# Active_Probe_Proto1.net
KiCad netlist of a schematic drawn in EAGLE
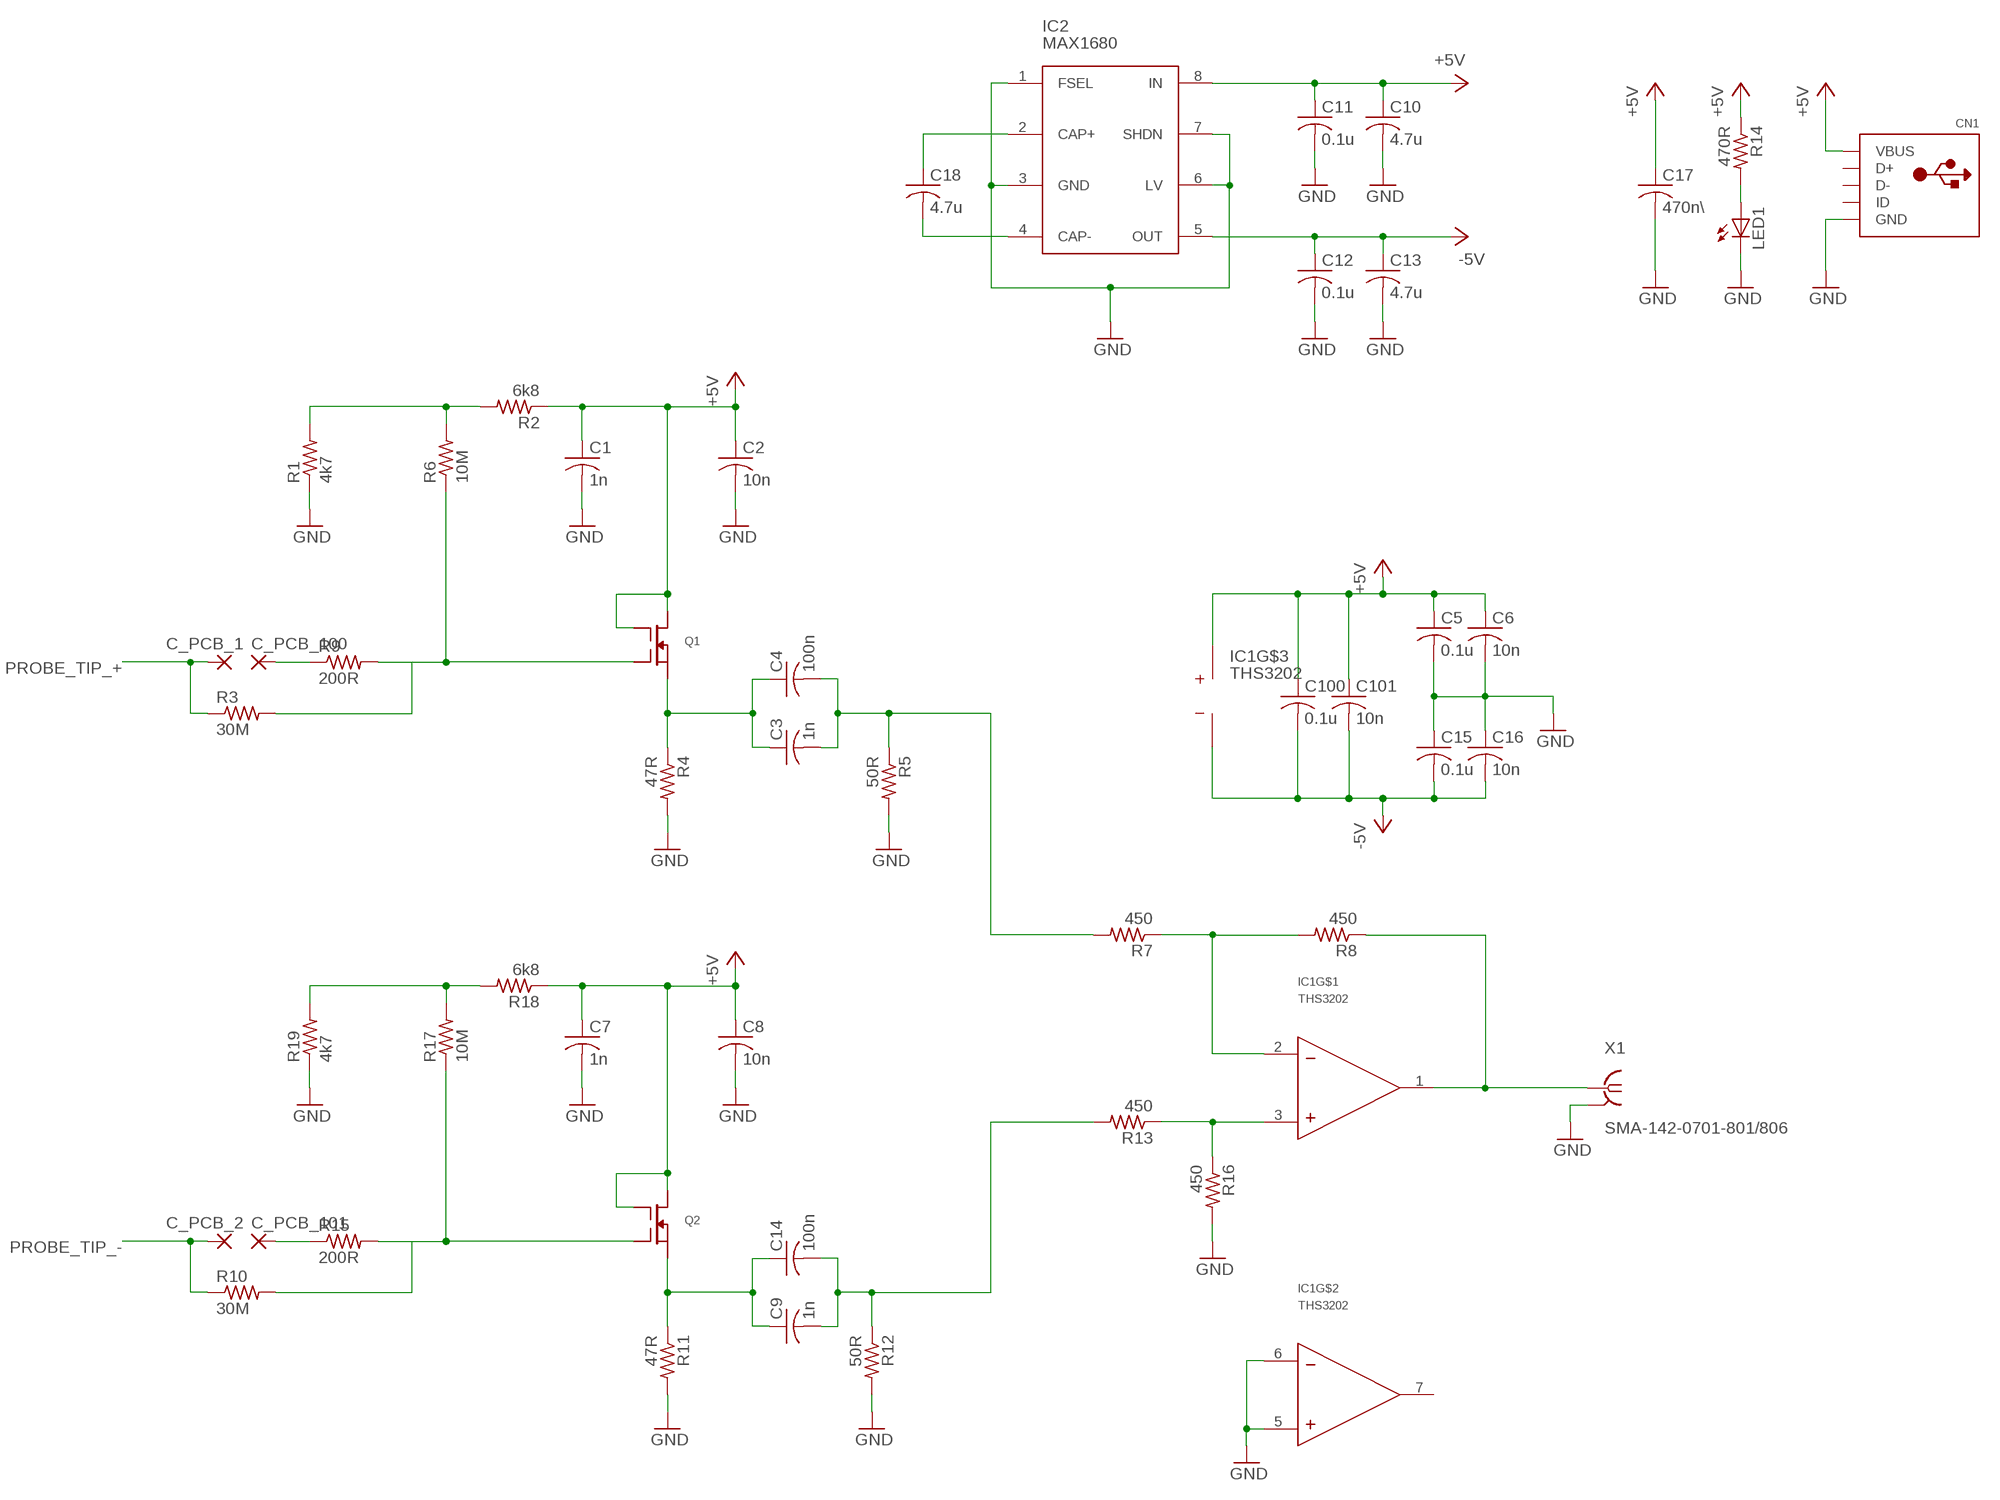
[diagram p0: schematic, sheet 1]

(export (version "E")
  (design (tool "Eeschema 10.0.6"))
  (components
    (comp (ref "C1")
      (value "1n")
      (footprint "eagle-import:C0805")
      (libsource (lib "eagle-import") (part "C-USC0805"))
    )
    (comp (ref "C2")
      (value "10n")
      (footprint "eagle-import:C0805")
      (libsource (lib "eagle-import") (part "C-USC0805"))
    )
    (comp (ref "C3")
      (value "1n")
      (footprint "eagle-import:C0805")
      (libsource (lib "eagle-import") (part "C-USC0805"))
    )
    (comp (ref "C4")
      (value "100n")
      (footprint "eagle-import:C0805")
      (libsource (lib "eagle-import") (part "C-USC0805"))
    )
    (comp (ref "C5")
      (value "0.1u")
      (footprint "eagle-import:C0805")
      (libsource (lib "eagle-import") (part "C-USC0805"))
    )
    (comp (ref "C6")
      (value "10n")
      (footprint "eagle-import:C0805")
      (libsource (lib "eagle-import") (part "C-USC0805"))
    )
    (comp (ref "C7")
      (value "1n")
      (footprint "eagle-import:C0805")
      (libsource (lib "eagle-import") (part "C-USC0805"))
    )
    (comp (ref "C8")
      (value "10n")
      (footprint "eagle-import:C0805")
      (libsource (lib "eagle-import") (part "C-USC0805"))
    )
    (comp (ref "C9")
      (value "1n")
      (footprint "eagle-import:C0805")
      (libsource (lib "eagle-import") (part "C-USC0805"))
    )
    (comp (ref "C10")
      (value "4.7u")
      (footprint "eagle-import:C0805")
      (libsource (lib "eagle-import") (part "C-USC0805"))
    )
    (comp (ref "C11")
      (value "0.1u")
      (footprint "eagle-import:C0805")
      (libsource (lib "eagle-import") (part "C-USC0805"))
    )
    (comp (ref "C12")
      (value "0.1u")
      (footprint "eagle-import:C0805")
      (libsource (lib "eagle-import") (part "C-USC0805"))
    )
    (comp (ref "C13")
      (value "4.7u")
      (footprint "eagle-import:C0805")
      (libsource (lib "eagle-import") (part "C-USC0805"))
    )
    (comp (ref "C14")
      (value "100n")
      (footprint "eagle-import:C0805")
      (libsource (lib "eagle-import") (part "C-USC0805"))
    )
    (comp (ref "C15")
      (value "0.1u")
      (footprint "eagle-import:C0805")
      (libsource (lib "eagle-import") (part "C-USC0805"))
    )
    (comp (ref "C16")
      (value "10n")
      (footprint "eagle-import:C0805")
      (libsource (lib "eagle-import") (part "C-USC0805"))
    )
    (comp (ref "C17")
      (value "470n\\")
      (footprint "eagle-import:C0805")
      (libsource (lib "eagle-import") (part "C-USC0805"))
    )
    (comp (ref "C18")
      (value "4.7u")
      (footprint "eagle-import:C0805")
      (libsource (lib "eagle-import") (part "C-USC0805"))
    )
    (comp (ref "C100")
      (value "0.1u")
      (footprint "eagle-import:C0805")
      (libsource (lib "eagle-import") (part "C-USC0805"))
    )
    (comp (ref "C101")
      (value "10n")
      (footprint "eagle-import:C0805")
      (libsource (lib "eagle-import") (part "C-USC0805"))
    )
    (comp (ref "CN1")
      (value "USBMINIB")
      (footprint "eagle-import:USB-MINIB")
      (libsource (lib "eagle-import") (part "USBMINIB"))
    )
    (comp (ref "C_PCB_1")
      (value "SMD5")
      (footprint "eagle-import:SMD2,54-5,08")
      (libsource (lib "eagle-import") (part "SMD5"))
    )
    (comp (ref "C_PCB_2")
      (value "SMD5")
      (footprint "eagle-import:SMD2,54-5,08")
      (libsource (lib "eagle-import") (part "SMD5"))
    )
    (comp (ref "C_PCB_100")
      (value "SMD5")
      (footprint "eagle-import:SMD2,54-5,08")
      (libsource (lib "eagle-import") (part "SMD5"))
    )
    (comp (ref "C_PCB_101")
      (value "SMD5")
      (footprint "eagle-import:SMD2,54-5,08")
      (libsource (lib "eagle-import") (part "SMD5"))
    )
    (comp (ref "IC1")
      (value "THS3202")
      (footprint "eagle-import:SOIC8")
      (libsource (lib "eagle-import") (part "THS3202"))
    )
    (comp (ref "IC2")
      (value "MAX1680")
      (footprint "eagle-import:SO8")
      (libsource (lib "eagle-import") (part "MAX1680/1"))
    )
    (comp (ref "LED1")
      (value "LED3MM")
      (footprint "eagle-import:LED3MM")
      (libsource (lib "eagle-import") (part "LED3MM"))
    )
    (comp (ref "Q1")
      (value "BF998")
      (footprint "eagle-import:SOT143B")
      (libsource (lib "eagle-import") (part "BF998"))
    )
    (comp (ref "Q2")
      (value "BF998")
      (footprint "eagle-import:SOT143B")
      (libsource (lib "eagle-import") (part "BF998"))
    )
    (comp (ref "R1")
      (value "4k7")
      (footprint "eagle-import:R0805")
      (libsource (lib "eagle-import") (part "R-US_R0805"))
    )
    (comp (ref "R2")
      (value "6k8")
      (footprint "eagle-import:R0805")
      (libsource (lib "eagle-import") (part "R-US_R0805"))
    )
    (comp (ref "R3")
      (value "30M")
      (footprint "eagle-import:R0805")
      (libsource (lib "eagle-import") (part "R-US_R0805"))
    )
    (comp (ref "R4")
      (value "47R")
      (footprint "eagle-import:R0805")
      (libsource (lib "eagle-import") (part "R-US_R0805"))
    )
    (comp (ref "R5")
      (value "50R")
      (footprint "eagle-import:R0805")
      (libsource (lib "eagle-import") (part "R-US_R0805"))
    )
    (comp (ref "R6")
      (value "10M")
      (footprint "eagle-import:R0805")
      (libsource (lib "eagle-import") (part "R-US_R0805"))
    )
    (comp (ref "R7")
      (value "450")
      (footprint "eagle-import:R0805")
      (libsource (lib "eagle-import") (part "R-US_R0805"))
    )
    (comp (ref "R8")
      (value "450")
      (footprint "eagle-import:R0805")
      (libsource (lib "eagle-import") (part "R-US_R0805"))
    )
    (comp (ref "R9")
      (value "200R")
      (footprint "eagle-import:R0805")
      (libsource (lib "eagle-import") (part "R-US_R0805"))
    )
    (comp (ref "R10")
      (value "30M")
      (footprint "eagle-import:R0805")
      (libsource (lib "eagle-import") (part "R-US_R0805"))
    )
    (comp (ref "R11")
      (value "47R")
      (footprint "eagle-import:R0805")
      (libsource (lib "eagle-import") (part "R-US_R0805"))
    )
    (comp (ref "R12")
      (value "50R")
      (footprint "eagle-import:R0805")
      (libsource (lib "eagle-import") (part "R-US_R0805"))
    )
    (comp (ref "R13")
      (value "450")
      (footprint "eagle-import:R0805")
      (libsource (lib "eagle-import") (part "R-US_R0805"))
    )
    (comp (ref "R14")
      (value "470R")
      (footprint "eagle-import:R0805")
      (libsource (lib "eagle-import") (part "R-US_R0805"))
    )
    (comp (ref "R15")
      (value "200R")
      (footprint "eagle-import:R0805")
      (libsource (lib "eagle-import") (part "R-US_R0805"))
    )
    (comp (ref "R16")
      (value "450")
      (footprint "eagle-import:R0805")
      (libsource (lib "eagle-import") (part "R-US_R0805"))
    )
    (comp (ref "R17")
      (value "10M")
      (footprint "eagle-import:R0805")
      (libsource (lib "eagle-import") (part "R-US_R0805"))
    )
    (comp (ref "R18")
      (value "6k8")
      (footprint "eagle-import:R0805")
      (libsource (lib "eagle-import") (part "R-US_R0805"))
    )
    (comp (ref "R19")
      (value "4k7")
      (footprint "eagle-import:R0805")
      (libsource (lib "eagle-import") (part "R-US_R0805"))
    )
    (comp (ref "X1")
      (value "SMA-142-0701-801/806")
      (footprint "eagle-import:J502-ND-142-0701-801_806")
      (fields (field (name "MF") "JOHNSON COMPONENTS") (field (name "MPN") "142-0701-801"))
      (libsource (lib "eagle-import") (part "SMA-142-0701-801/806"))
    )
  )
  (nets
    (net (code "1") (name "+5V") (class "Default")
      (node (ref "C1") (pin "1") (pinfunction "1_1") (pintype "passive"))
      (node (ref "C10") (pin "1") (pinfunction "1_1") (pintype "passive"))
      (node (ref "C100") (pin "1") (pinfunction "1_1") (pintype "passive"))
      (node (ref "C101") (pin "1") (pinfunction "1_1") (pintype "passive"))
      (node (ref "C11") (pin "1") (pinfunction "1_1") (pintype "passive"))
      (node (ref "C17") (pin "1") (pinfunction "1_1") (pintype "passive"))
      (node (ref "C2") (pin "1") (pinfunction "1_1") (pintype "passive"))
      (node (ref "C5") (pin "1") (pinfunction "1_1") (pintype "passive"))
      (node (ref "C6") (pin "1") (pinfunction "1_1") (pintype "passive"))
      (node (ref "C7") (pin "1") (pinfunction "1_1") (pintype "passive"))
      (node (ref "C8") (pin "1") (pinfunction "1_1") (pintype "passive"))
      (node (ref "CN1") (pin "VBUS") (pinfunction "VBUS_VBUS") (pintype "power_in"))
      (node (ref "IC1") (pin "8") (pinfunction "VCC_8") (pintype "power_in"))
      (node (ref "IC2") (pin "8") (pinfunction "IN_8") (pintype "bidirectional"))
      (node (ref "Q1") (pin "2") (pinfunction "D_2") (pintype "bidirectional"))
      (node (ref "Q1") (pin "3") (pinfunction "G2_3") (pintype "bidirectional"))
      (node (ref "Q2") (pin "2") (pinfunction "D_2") (pintype "bidirectional"))
      (node (ref "Q2") (pin "3") (pinfunction "G2_3") (pintype "bidirectional"))
      (node (ref "R14") (pin "1") (pinfunction "1_1") (pintype "passive"))
      (node (ref "R18") (pin "1") (pinfunction "1_1") (pintype "passive"))
      (node (ref "R2") (pin "1") (pinfunction "1_1") (pintype "passive"))
    )
    (net (code "2") (name "-5V") (class "Default")
      (node (ref "C100") (pin "2") (pinfunction "2_2") (pintype "passive"))
      (node (ref "C101") (pin "2") (pinfunction "2_2") (pintype "passive"))
      (node (ref "C12") (pin "1") (pinfunction "1_1") (pintype "passive"))
      (node (ref "C13") (pin "1") (pinfunction "1_1") (pintype "passive"))
      (node (ref "C15") (pin "2") (pinfunction "2_2") (pintype "passive"))
      (node (ref "C16") (pin "2") (pinfunction "2_2") (pintype "passive"))
      (node (ref "IC1") (pin "4") (pinfunction "GND_4") (pintype "power_in"))
      (node (ref "IC2") (pin "5") (pinfunction "OUT_5") (pintype "bidirectional"))
    )
    (net (code "3") (name "/PROBE_TIP_+") (class "Default")
      (node (ref "C_PCB_1") (pin "1") (pinfunction "P_1") (pintype "passive"))
      (node (ref "R3") (pin "1") (pinfunction "1_1") (pintype "passive"))
    )
    (net (code "4") (name "/PROBE_TIP_-") (class "Default")
      (node (ref "C_PCB_2") (pin "1") (pinfunction "P_1") (pintype "passive"))
      (node (ref "R10") (pin "1") (pinfunction "1_1") (pintype "passive"))
    )
    (net (code "5") (name "GND") (class "Default")
      (node (ref "C1") (pin "2") (pinfunction "2_2") (pintype "passive"))
      (node (ref "C10") (pin "2") (pinfunction "2_2") (pintype "passive"))
      (node (ref "C11") (pin "2") (pinfunction "2_2") (pintype "passive"))
      (node (ref "C12") (pin "2") (pinfunction "2_2") (pintype "passive"))
      (node (ref "C13") (pin "2") (pinfunction "2_2") (pintype "passive"))
      (node (ref "C15") (pin "1") (pinfunction "1_1") (pintype "passive"))
      (node (ref "C16") (pin "1") (pinfunction "1_1") (pintype "passive"))
      (node (ref "C17") (pin "2") (pinfunction "2_2") (pintype "passive"))
      (node (ref "C2") (pin "2") (pinfunction "2_2") (pintype "passive"))
      (node (ref "C5") (pin "2") (pinfunction "2_2") (pintype "passive"))
      (node (ref "C6") (pin "2") (pinfunction "2_2") (pintype "passive"))
      (node (ref "C7") (pin "2") (pinfunction "2_2") (pintype "passive"))
      (node (ref "C8") (pin "2") (pinfunction "2_2") (pintype "passive"))
      (node (ref "CN1") (pin "GND") (pinfunction "GND_GND") (pintype "power_in"))
      (node (ref "IC1") (pin "5") (pinfunction "IN+_5") (pintype "input"))
      (node (ref "IC1") (pin "6") (pinfunction "IN-_6") (pintype "input"))
      (node (ref "IC2") (pin "1") (pinfunction "FSEL_1") (pintype "bidirectional"))
      (node (ref "IC2") (pin "3") (pinfunction "GND_3") (pintype "bidirectional"))
      (node (ref "IC2") (pin "6") (pinfunction "LV_6") (pintype "bidirectional"))
      (node (ref "IC2") (pin "7") (pinfunction "SHDN_7") (pintype "bidirectional"))
      (node (ref "LED1") (pin "K") (pinfunction "C_K") (pintype "passive"))
      (node (ref "R1") (pin "1") (pinfunction "1_1") (pintype "passive"))
      (node (ref "R11") (pin "2") (pinfunction "2_2") (pintype "passive"))
      (node (ref "R12") (pin "2") (pinfunction "2_2") (pintype "passive"))
      (node (ref "R16") (pin "2") (pinfunction "2_2") (pintype "passive"))
      (node (ref "R19") (pin "1") (pinfunction "1_1") (pintype "passive"))
      (node (ref "R4") (pin "2") (pinfunction "2_2") (pintype "passive"))
      (node (ref "R5") (pin "2") (pinfunction "2_2") (pintype "passive"))
      (node (ref "X1") (pin "G@1") (pinfunction "GND_G@1") (pintype "power_in"))
    )
    (net (code "6") (name "Net-(C3-Pad2)") (class "Default")
      (node (ref "C3") (pin "2") (pinfunction "2_2") (pintype "passive"))
      (node (ref "C4") (pin "2") (pinfunction "2_2") (pintype "passive"))
      (node (ref "R5") (pin "1") (pinfunction "1_1") (pintype "passive"))
      (node (ref "R7") (pin "2") (pinfunction "2_2") (pintype "passive"))
    )
    (net (code "7") (name "Net-(C14-Pad2)") (class "Default")
      (node (ref "C14") (pin "2") (pinfunction "2_2") (pintype "passive"))
      (node (ref "C9") (pin "2") (pinfunction "2_2") (pintype "passive"))
      (node (ref "R12") (pin "1") (pinfunction "1_1") (pintype "passive"))
      (node (ref "R13") (pin "2") (pinfunction "2_2") (pintype "passive"))
    )
    (net (code "8") (name "Net-(C_PCB_100-P)") (class "Default")
      (node (ref "C_PCB_100") (pin "1") (pinfunction "P_1") (pintype "passive"))
      (node (ref "R9") (pin "1") (pinfunction "1_1") (pintype "passive"))
    )
    (net (code "9") (name "Net-(C_PCB_101-P)") (class "Default")
      (node (ref "C_PCB_101") (pin "1") (pinfunction "P_1") (pintype "passive"))
      (node (ref "R15") (pin "1") (pinfunction "1_1") (pintype "passive"))
    )
    (net (code "10") (name "Net-(IC1A-IN+)") (class "Default")
      (node (ref "IC1") (pin "3") (pinfunction "IN+_3") (pintype "input"))
      (node (ref "R13") (pin "1") (pinfunction "1_1") (pintype "passive"))
      (node (ref "R16") (pin "1") (pinfunction "1_1") (pintype "passive"))
    )
    (net (code "11") (name "Net-(IC1A-IN-)") (class "Default")
      (node (ref "IC1") (pin "2") (pinfunction "IN-_2") (pintype "input"))
      (node (ref "R7") (pin "1") (pinfunction "1_1") (pintype "passive"))
      (node (ref "R8") (pin "2") (pinfunction "2_2") (pintype "passive"))
    )
    (net (code "12") (name "Net-(IC1A-OUT)") (class "Default")
      (node (ref "IC1") (pin "1") (pinfunction "OUT_1") (pintype "output"))
      (node (ref "R8") (pin "1") (pinfunction "1_1") (pintype "passive"))
      (node (ref "X1") (pin "1") (pinfunction "1_1") (pintype "passive"))
    )
    (net (code "13") (name "Net-(IC2-CAP+)") (class "Default")
      (node (ref "C18") (pin "1") (pinfunction "1_1") (pintype "passive"))
      (node (ref "IC2") (pin "2") (pinfunction "CAP+_2") (pintype "bidirectional"))
    )
    (net (code "14") (name "Net-(IC2-CAP-)") (class "Default")
      (node (ref "C18") (pin "2") (pinfunction "2_2") (pintype "passive"))
      (node (ref "IC2") (pin "4") (pinfunction "CAP-_4") (pintype "bidirectional"))
    )
    (net (code "15") (name "Net-(LED1-PadA)") (class "Default")
      (node (ref "LED1") (pin "A") (pinfunction "A_A") (pintype "passive"))
      (node (ref "R14") (pin "2") (pinfunction "2_2") (pintype "passive"))
    )
    (net (code "16") (name "Net-(Q1-G1)") (class "Default")
      (node (ref "Q1") (pin "4") (pinfunction "G1_4") (pintype "bidirectional"))
      (node (ref "R3") (pin "2") (pinfunction "2_2") (pintype "passive"))
      (node (ref "R6") (pin "1") (pinfunction "1_1") (pintype "passive"))
      (node (ref "R9") (pin "2") (pinfunction "2_2") (pintype "passive"))
    )
    (net (code "17") (name "Net-(Q1-S)") (class "Default")
      (node (ref "C3") (pin "1") (pinfunction "1_1") (pintype "passive"))
      (node (ref "C4") (pin "1") (pinfunction "1_1") (pintype "passive"))
      (node (ref "Q1") (pin "1") (pinfunction "S_1") (pintype "bidirectional"))
      (node (ref "R4") (pin "1") (pinfunction "1_1") (pintype "passive"))
    )
    (net (code "18") (name "Net-(Q2-G1)") (class "Default")
      (node (ref "Q2") (pin "4") (pinfunction "G1_4") (pintype "bidirectional"))
      (node (ref "R10") (pin "2") (pinfunction "2_2") (pintype "passive"))
      (node (ref "R15") (pin "2") (pinfunction "2_2") (pintype "passive"))
      (node (ref "R17") (pin "1") (pinfunction "1_1") (pintype "passive"))
    )
    (net (code "19") (name "Net-(Q2-S)") (class "Default")
      (node (ref "C14") (pin "1") (pinfunction "1_1") (pintype "passive"))
      (node (ref "C9") (pin "1") (pinfunction "1_1") (pintype "passive"))
      (node (ref "Q2") (pin "1") (pinfunction "S_1") (pintype "bidirectional"))
      (node (ref "R11") (pin "1") (pinfunction "1_1") (pintype "passive"))
    )
    (net (code "20") (name "Net-(R1-Pad2)") (class "Default")
      (node (ref "R1") (pin "2") (pinfunction "2_2") (pintype "passive"))
      (node (ref "R2") (pin "2") (pinfunction "2_2") (pintype "passive"))
      (node (ref "R6") (pin "2") (pinfunction "2_2") (pintype "passive"))
    )
    (net (code "21") (name "Net-(R17-Pad2)") (class "Default")
      (node (ref "R17") (pin "2") (pinfunction "2_2") (pintype "passive"))
      (node (ref "R18") (pin "2") (pinfunction "2_2") (pintype "passive"))
      (node (ref "R19") (pin "2") (pinfunction "2_2") (pintype "passive"))
    )
    (net (code "22") (name "unconnected-(CN1-PadD+)") (class "Default")
      (node (ref "CN1") (pin "D+") (pinfunction "D+_D+") (pintype "bidirectional"))
    )
    (net (code "23") (name "unconnected-(CN1-PadD-)") (class "Default")
      (node (ref "CN1") (pin "D-") (pinfunction "D-_D-") (pintype "bidirectional"))
    )
    (net (code "24") (name "unconnected-(CN1-PadID)") (class "Default")
      (node (ref "CN1") (pin "ID") (pinfunction "ID_ID") (pintype "bidirectional"))
    )
    (net (code "25") (name "unconnected-(IC1B-OUT-Pad7)") (class "Default")
      (node (ref "IC1") (pin "7") (pinfunction "OUT_7") (pintype "output"))
    )
  )
)
